# mimic4688.net
KiCad netlist of a schematic drawn in EAGLE
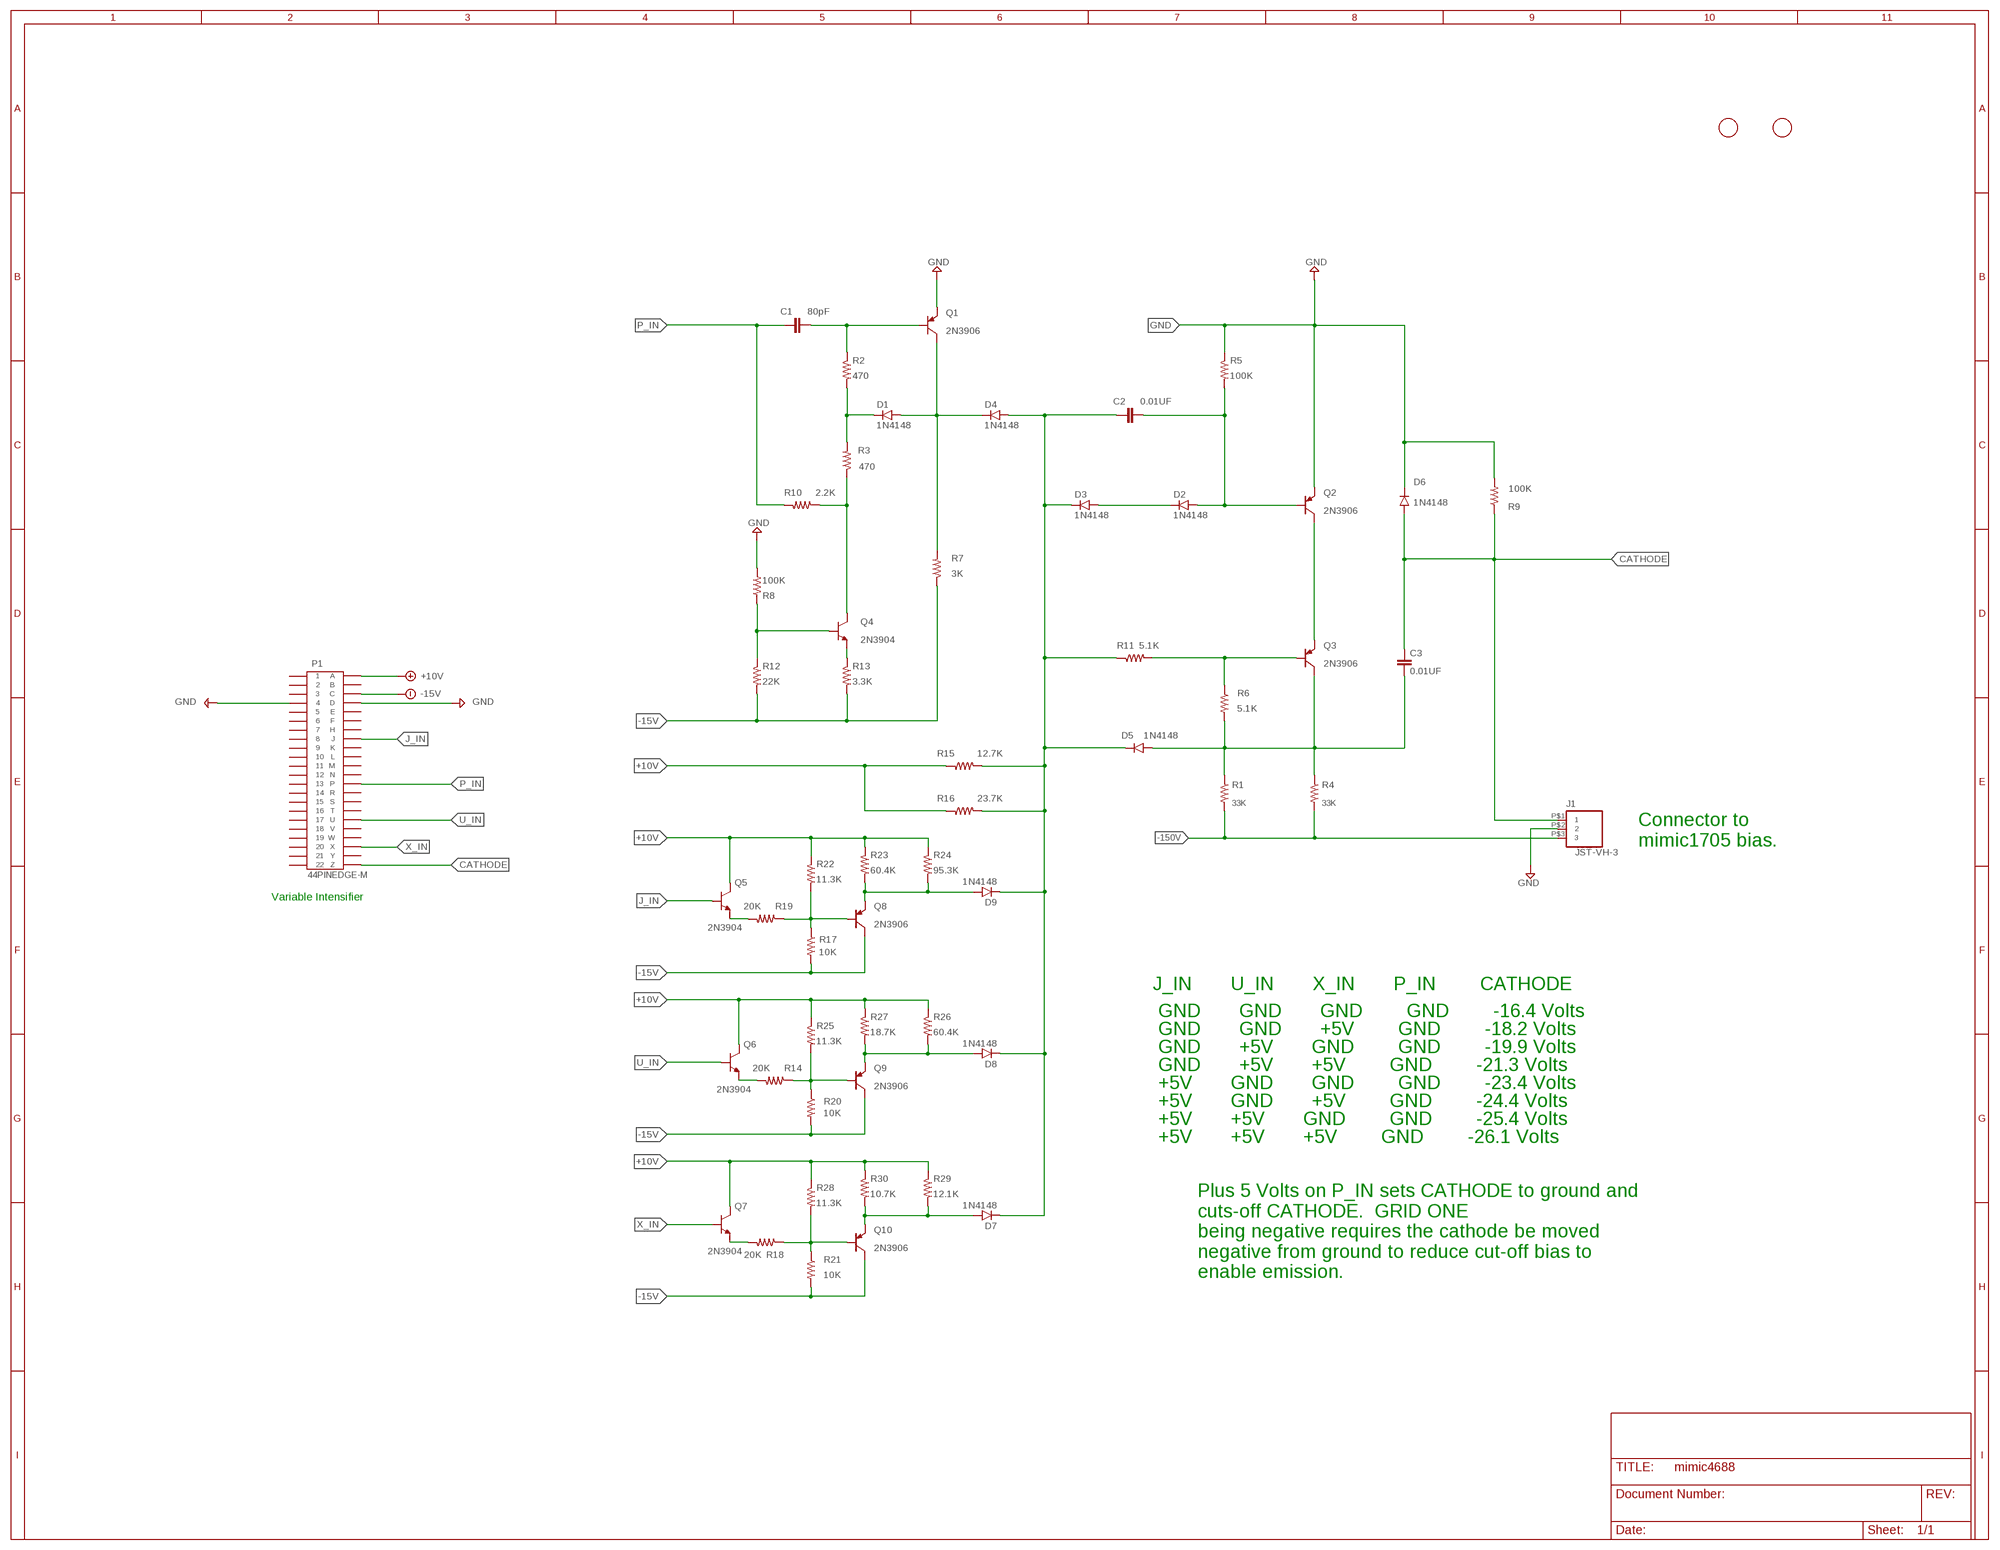
[diagram p0: schematic, sheet 1]

(export (version "E")
  (design (tool "Eeschema 10.0.6"))
  (components
    (comp (ref "C1")
      (value "80pF")
      (footprint "eagle-import:5MM_TH")
      (libsource (lib "eagle-import") (part "CAP_5MM"))
    )
    (comp (ref "C2")
      (value "0.01UF")
      (footprint "eagle-import:5MM_TH")
      (libsource (lib "eagle-import") (part "CAP_5MM"))
    )
    (comp (ref "C3")
      (value "0.01UF")
      (footprint "eagle-import:5MM_TH")
      (libsource (lib "eagle-import") (part "CAP_5MM"))
    )
    (comp (ref "D1")
      (value "1N4148")
      (footprint "eagle-import:DO35-7")
      (libsource (lib "eagle-import") (part "1N4148"))
    )
    (comp (ref "D2")
      (value "1N4148")
      (footprint "eagle-import:DO35-7")
      (libsource (lib "eagle-import") (part "1N4148"))
    )
    (comp (ref "D3")
      (value "1N4148")
      (footprint "eagle-import:DO35-7")
      (libsource (lib "eagle-import") (part "1N4148"))
    )
    (comp (ref "D4")
      (value "1N4148")
      (footprint "eagle-import:DO35-7")
      (libsource (lib "eagle-import") (part "1N4148"))
    )
    (comp (ref "D5")
      (value "1N4148")
      (footprint "eagle-import:DO35-7")
      (libsource (lib "eagle-import") (part "1N4148"))
    )
    (comp (ref "D6")
      (value "1N4148")
      (footprint "eagle-import:DO35-7")
      (libsource (lib "eagle-import") (part "1N4148"))
    )
    (comp (ref "D7")
      (value "1N4148")
      (footprint "eagle-import:DO35-7")
      (libsource (lib "eagle-import") (part "1N4148"))
    )
    (comp (ref "D8")
      (value "1N4148")
      (footprint "eagle-import:DO35-7")
      (libsource (lib "eagle-import") (part "1N4148"))
    )
    (comp (ref "D9")
      (value "1N4148")
      (footprint "eagle-import:DO35-7")
      (libsource (lib "eagle-import") (part "1N4148"))
    )
    (comp (ref "J1")
      (value "JST-VH-3")
      (footprint "eagle-import:VHR-3N")
      (libsource (lib "eagle-import") (part "JST-VH-3"))
    )
    (comp (ref "P1")
      (value "44PINEDGE-M")
      (footprint "eagle-import:44PINEDGE")
      (libsource (lib "eagle-import") (part "44PINEDGE-M"))
    )
    (comp (ref "Q1")
      (value "2N3906")
      (footprint "eagle-import:TO92")
      (libsource (lib "eagle-import") (part "2N3906"))
    )
    (comp (ref "Q2")
      (value "2N3906")
      (footprint "eagle-import:TO92")
      (libsource (lib "eagle-import") (part "2N3906"))
    )
    (comp (ref "Q3")
      (value "2N3906")
      (footprint "eagle-import:TO92")
      (libsource (lib "eagle-import") (part "2N3906"))
    )
    (comp (ref "Q4")
      (value "2N3904")
      (footprint "eagle-import:TO92")
      (libsource (lib "eagle-import") (part "2N3904"))
    )
    (comp (ref "Q5")
      (value "2N3904")
      (footprint "eagle-import:TO92")
      (libsource (lib "eagle-import") (part "2N3904"))
    )
    (comp (ref "Q6")
      (value "2N3904")
      (footprint "eagle-import:TO92")
      (libsource (lib "eagle-import") (part "2N3904"))
    )
    (comp (ref "Q7")
      (value "2N3904")
      (footprint "eagle-import:TO92")
      (libsource (lib "eagle-import") (part "2N3904"))
    )
    (comp (ref "Q8")
      (value "2N3906")
      (footprint "eagle-import:TO92")
      (libsource (lib "eagle-import") (part "2N3906"))
    )
    (comp (ref "Q9")
      (value "2N3906")
      (footprint "eagle-import:TO92")
      (libsource (lib "eagle-import") (part "2N3906"))
    )
    (comp (ref "Q10")
      (value "2N3906")
      (footprint "eagle-import:TO92")
      (libsource (lib "eagle-import") (part "2N3906"))
    )
    (comp (ref "R1")
      (value "33K")
      (footprint "eagle-import:RR02")
      (libsource (lib "eagle-import") (part "RES33K2W"))
    )
    (comp (ref "R2")
      (value "470")
      (footprint "eagle-import:0207_10")
      (libsource (lib "eagle-import") (part "R-1/4WATT"))
    )
    (comp (ref "R3")
      (value "470")
      (footprint "eagle-import:0207_10")
      (libsource (lib "eagle-import") (part "R-1/4WATT"))
    )
    (comp (ref "R4")
      (value "33K")
      (footprint "eagle-import:RR02")
      (libsource (lib "eagle-import") (part "RES33K2W"))
    )
    (comp (ref "R5")
      (value "100K")
      (footprint "eagle-import:0207_10")
      (libsource (lib "eagle-import") (part "R-1/4WATT"))
    )
    (comp (ref "R6")
      (value "5.1K")
      (footprint "eagle-import:0207_10")
      (libsource (lib "eagle-import") (part "R-1/4WATT"))
    )
    (comp (ref "R7")
      (value "3K")
      (footprint "eagle-import:0207_10")
      (libsource (lib "eagle-import") (part "R-1/4WATT"))
    )
    (comp (ref "R8")
      (value "100K")
      (footprint "eagle-import:0207_10")
      (libsource (lib "eagle-import") (part "R-1/4WATT"))
    )
    (comp (ref "R9")
      (value "100K")
      (footprint "eagle-import:0207_10")
      (libsource (lib "eagle-import") (part "R-1/4WATT"))
    )
    (comp (ref "R10")
      (value "2.2K")
      (footprint "eagle-import:0207_10")
      (libsource (lib "eagle-import") (part "R-1/4WATT"))
    )
    (comp (ref "R11")
      (value "5.1K")
      (footprint "eagle-import:0207_10")
      (libsource (lib "eagle-import") (part "R-1/4WATT"))
    )
    (comp (ref "R12")
      (value "22K")
      (footprint "eagle-import:0207_10")
      (libsource (lib "eagle-import") (part "R-1/4WATT"))
    )
    (comp (ref "R13")
      (value "3.3K")
      (footprint "eagle-import:0207_10")
      (libsource (lib "eagle-import") (part "R-1/4WATT"))
    )
    (comp (ref "R14")
      (value "20K")
      (footprint "eagle-import:0207_10")
      (libsource (lib "eagle-import") (part "R-1/4WATT"))
    )
    (comp (ref "R15")
      (value "12.7K")
      (footprint "eagle-import:0207_10")
      (libsource (lib "eagle-import") (part "R-1/4WATT"))
    )
    (comp (ref "R16")
      (value "23.7K")
      (footprint "eagle-import:0207_10")
      (libsource (lib "eagle-import") (part "R-1/4WATT"))
    )
    (comp (ref "R17")
      (value "10K")
      (footprint "eagle-import:0207_10")
      (libsource (lib "eagle-import") (part "R-1/4WATT"))
    )
    (comp (ref "R18")
      (value "20K")
      (footprint "eagle-import:0207_10")
      (libsource (lib "eagle-import") (part "R-1/4WATT"))
    )
    (comp (ref "R19")
      (value "20K")
      (footprint "eagle-import:0207_10")
      (libsource (lib "eagle-import") (part "R-1/4WATT"))
    )
    (comp (ref "R20")
      (value "10K")
      (footprint "eagle-import:0207_10")
      (libsource (lib "eagle-import") (part "R-1/4WATT"))
    )
    (comp (ref "R21")
      (value "10K")
      (footprint "eagle-import:0207_10")
      (libsource (lib "eagle-import") (part "R-1/4WATT"))
    )
    (comp (ref "R22")
      (value "11.3K")
      (footprint "eagle-import:0207_10")
      (libsource (lib "eagle-import") (part "R-1/4WATT"))
    )
    (comp (ref "R23")
      (value "60.4K")
      (footprint "eagle-import:0207_10")
      (libsource (lib "eagle-import") (part "R-1/4WATT"))
    )
    (comp (ref "R24")
      (value "95.3K")
      (footprint "eagle-import:0207_10")
      (libsource (lib "eagle-import") (part "R-1/4WATT"))
    )
    (comp (ref "R25")
      (value "11.3K")
      (footprint "eagle-import:0207_10")
      (libsource (lib "eagle-import") (part "R-1/4WATT"))
    )
    (comp (ref "R26")
      (value "60.4K")
      (footprint "eagle-import:0207_10")
      (libsource (lib "eagle-import") (part "R-1/4WATT"))
    )
    (comp (ref "R27")
      (value "18.7K")
      (footprint "eagle-import:0207_10")
      (libsource (lib "eagle-import") (part "R-1/4WATT"))
    )
    (comp (ref "R28")
      (value "11.3K")
      (footprint "eagle-import:0207_10")
      (libsource (lib "eagle-import") (part "R-1/4WATT"))
    )
    (comp (ref "R29")
      (value "12.1K")
      (footprint "eagle-import:0207_10")
      (libsource (lib "eagle-import") (part "R-1/4WATT"))
    )
    (comp (ref "R30")
      (value "10.7K")
      (footprint "eagle-import:0207_10")
      (libsource (lib "eagle-import") (part "R-1/4WATT"))
    )
    (comp (ref "U$1")
      (value "FIDUCIAL")
      (footprint "eagle-import:FIDUCIAL_1MM")
      (libsource (lib "eagle-import") (part "FIDUCIAL"))
    )
    (comp (ref "U$2")
      (value "FIDUCIAL")
      (footprint "eagle-import:FIDUCIAL_1MM")
      (libsource (lib "eagle-import") (part "FIDUCIAL"))
    )
  )
  (nets
    (net (code "1") (name "+10V") (class "Default")
      (node (ref "P1") (pin "A") (pinfunction "A_A") (pintype "passive"))
      (node (ref "Q5") (pin "3") (pinfunction "C_3") (pintype "passive"))
      (node (ref "Q6") (pin "3") (pinfunction "C_3") (pintype "passive"))
      (node (ref "Q7") (pin "3") (pinfunction "C_3") (pintype "passive"))
      (node (ref "R15") (pin "1") (pinfunction "P$1_1") (pintype "passive"))
      (node (ref "R16") (pin "1") (pinfunction "P$1_1") (pintype "passive"))
      (node (ref "R22") (pin "1") (pinfunction "P$1_1") (pintype "passive"))
      (node (ref "R23") (pin "1") (pinfunction "P$1_1") (pintype "passive"))
      (node (ref "R24") (pin "1") (pinfunction "P$1_1") (pintype "passive"))
      (node (ref "R25") (pin "1") (pinfunction "P$1_1") (pintype "passive"))
      (node (ref "R26") (pin "1") (pinfunction "P$1_1") (pintype "passive"))
      (node (ref "R27") (pin "1") (pinfunction "P$1_1") (pintype "passive"))
      (node (ref "R28") (pin "1") (pinfunction "P$1_1") (pintype "passive"))
      (node (ref "R29") (pin "1") (pinfunction "P$1_1") (pintype "passive"))
      (node (ref "R30") (pin "1") (pinfunction "P$1_1") (pintype "passive"))
    )
    (net (code "2") (name "-15V") (class "Default")
      (node (ref "P1") (pin "C") (pinfunction "C_C") (pintype "passive"))
      (node (ref "Q10") (pin "1") (pinfunction "C_1") (pintype "passive"))
      (node (ref "Q8") (pin "1") (pinfunction "C_1") (pintype "passive"))
      (node (ref "Q9") (pin "1") (pinfunction "C_1") (pintype "passive"))
      (node (ref "R12") (pin "2") (pinfunction "P$2_2") (pintype "passive"))
      (node (ref "R13") (pin "2") (pinfunction "P$2_2") (pintype "passive"))
      (node (ref "R17") (pin "2") (pinfunction "P$2_2") (pintype "passive"))
      (node (ref "R20") (pin "2") (pinfunction "P$2_2") (pintype "passive"))
      (node (ref "R21") (pin "2") (pinfunction "P$2_2") (pintype "passive"))
      (node (ref "R7") (pin "1") (pinfunction "P$1_1") (pintype "passive"))
    )
    (net (code "3") (name "-150V") (class "Default")
      (node (ref "J1") (pin "P$3") (pinfunction "3_P$3") (pintype "bidirectional"))
      (node (ref "R1") (pin "2") (pinfunction "P$2_2") (pintype "passive"))
      (node (ref "R4") (pin "2") (pinfunction "P$2_2") (pintype "passive"))
    )
    (net (code "4") (name "CATHODE") (class "Default")
      (node (ref "C3") (pin "1") (pinfunction "1_1") (pintype "passive"))
      (node (ref "D6") (pin "A") (pinfunction "A_A") (pintype "passive"))
      (node (ref "J1") (pin "P$1") (pinfunction "1_P$1") (pintype "bidirectional"))
      (node (ref "P1") (pin "Z") (pinfunction "Z_Z") (pintype "passive"))
      (node (ref "R9") (pin "1") (pinfunction "P$1_1") (pintype "passive"))
    )
    (net (code "5") (name "GND") (class "Default")
      (node (ref "D6") (pin "C") (pinfunction "C_C") (pintype "passive"))
      (node (ref "J1") (pin "P$2") (pinfunction "2_P$2") (pintype "bidirectional"))
      (node (ref "P1") (pin "4") (pinfunction "4_4") (pintype "passive"))
      (node (ref "P1") (pin "D") (pinfunction "D_D") (pintype "passive"))
      (node (ref "Q1") (pin "3") (pinfunction "E_3") (pintype "passive"))
      (node (ref "Q2") (pin "3") (pinfunction "E_3") (pintype "passive"))
      (node (ref "R5") (pin "1") (pinfunction "P$1_1") (pintype "passive"))
      (node (ref "R8") (pin "2") (pinfunction "P$2_2") (pintype "passive"))
      (node (ref "R9") (pin "2") (pinfunction "P$2_2") (pintype "passive"))
    )
    (net (code "6") (name "J_IN") (class "Default")
      (node (ref "P1") (pin "J") (pinfunction "J_J") (pintype "passive"))
      (node (ref "Q5") (pin "2") (pinfunction "B_2") (pintype "passive"))
    )
    (net (code "7") (name "Net-(D2-PadC)") (class "Default")
      (node (ref "D2") (pin "C") (pinfunction "C_C") (pintype "passive"))
      (node (ref "D3") (pin "A") (pinfunction "A_A") (pintype "passive"))
    )
    (net (code "8") (name "Net-(Q1-B)") (class "Default")
      (node (ref "C1") (pin "2") (pinfunction "2_2") (pintype "passive"))
      (node (ref "Q1") (pin "2") (pinfunction "B_2") (pintype "passive"))
      (node (ref "R2") (pin "1") (pinfunction "P$1_1") (pintype "passive"))
    )
    (net (code "9") (name "Net-(Q1-C)") (class "Default")
      (node (ref "D1") (pin "A") (pinfunction "A_A") (pintype "passive"))
      (node (ref "D4") (pin "C") (pinfunction "C_C") (pintype "passive"))
      (node (ref "Q1") (pin "1") (pinfunction "C_1") (pintype "passive"))
      (node (ref "R7") (pin "2") (pinfunction "P$2_2") (pintype "passive"))
    )
    (net (code "10") (name "Net-(Q2-B)") (class "Default")
      (node (ref "C2") (pin "2") (pinfunction "2_2") (pintype "passive"))
      (node (ref "D2") (pin "A") (pinfunction "A_A") (pintype "passive"))
      (node (ref "Q2") (pin "2") (pinfunction "B_2") (pintype "passive"))
      (node (ref "R5") (pin "2") (pinfunction "P$2_2") (pintype "passive"))
    )
    (net (code "11") (name "Net-(Q2-C)") (class "Default")
      (node (ref "Q2") (pin "1") (pinfunction "C_1") (pintype "passive"))
      (node (ref "Q3") (pin "3") (pinfunction "E_3") (pintype "passive"))
    )
    (net (code "12") (name "Net-(Q3-B)") (class "Default")
      (node (ref "Q3") (pin "2") (pinfunction "B_2") (pintype "passive"))
      (node (ref "R11") (pin "2") (pinfunction "P$2_2") (pintype "passive"))
      (node (ref "R6") (pin "1") (pinfunction "P$1_1") (pintype "passive"))
    )
    (net (code "13") (name "Net-(Q3-C)") (class "Default")
      (node (ref "C3") (pin "2") (pinfunction "2_2") (pintype "passive"))
      (node (ref "D5") (pin "A") (pinfunction "A_A") (pintype "passive"))
      (node (ref "Q3") (pin "1") (pinfunction "C_1") (pintype "passive"))
      (node (ref "R1") (pin "1") (pinfunction "P$1_1") (pintype "passive"))
      (node (ref "R4") (pin "1") (pinfunction "P$1_1") (pintype "passive"))
      (node (ref "R6") (pin "2") (pinfunction "P$2_2") (pintype "passive"))
    )
    (net (code "14") (name "Net-(Q4-B)") (class "Default")
      (node (ref "Q4") (pin "2") (pinfunction "B_2") (pintype "passive"))
      (node (ref "R12") (pin "1") (pinfunction "P$1_1") (pintype "passive"))
      (node (ref "R8") (pin "1") (pinfunction "P$1_1") (pintype "passive"))
    )
    (net (code "15") (name "Net-(Q4-C)") (class "Default")
      (node (ref "Q4") (pin "3") (pinfunction "C_3") (pintype "passive"))
      (node (ref "R10") (pin "1") (pinfunction "P$1_1") (pintype "passive"))
      (node (ref "R3") (pin "1") (pinfunction "P$1_1") (pintype "passive"))
    )
    (net (code "16") (name "Net-(Q4-E)") (class "Default")
      (node (ref "Q4") (pin "1") (pinfunction "E_1") (pintype "passive"))
      (node (ref "R13") (pin "1") (pinfunction "P$1_1") (pintype "passive"))
    )
    (net (code "17") (name "Net-(Q5-E)") (class "Default")
      (node (ref "Q5") (pin "1") (pinfunction "E_1") (pintype "passive"))
      (node (ref "R19") (pin "2") (pinfunction "P$2_2") (pintype "passive"))
    )
    (net (code "18") (name "Net-(Q6-E)") (class "Default")
      (node (ref "Q6") (pin "1") (pinfunction "E_1") (pintype "passive"))
      (node (ref "R14") (pin "2") (pinfunction "P$2_2") (pintype "passive"))
    )
    (net (code "19") (name "Net-(Q7-E)") (class "Default")
      (node (ref "Q7") (pin "1") (pinfunction "E_1") (pintype "passive"))
      (node (ref "R18") (pin "2") (pinfunction "P$2_2") (pintype "passive"))
    )
    (net (code "20") (name "Net-(Q8-B)") (class "Default")
      (node (ref "Q8") (pin "2") (pinfunction "B_2") (pintype "passive"))
      (node (ref "R17") (pin "1") (pinfunction "P$1_1") (pintype "passive"))
      (node (ref "R19") (pin "1") (pinfunction "P$1_1") (pintype "passive"))
      (node (ref "R22") (pin "2") (pinfunction "P$2_2") (pintype "passive"))
    )
    (net (code "21") (name "Net-(Q8-E)") (class "Default")
      (node (ref "D9") (pin "A") (pinfunction "A_A") (pintype "passive"))
      (node (ref "Q8") (pin "3") (pinfunction "E_3") (pintype "passive"))
      (node (ref "R23") (pin "2") (pinfunction "P$2_2") (pintype "passive"))
      (node (ref "R24") (pin "2") (pinfunction "P$2_2") (pintype "passive"))
    )
    (net (code "22") (name "Net-(Q9-B)") (class "Default")
      (node (ref "Q9") (pin "2") (pinfunction "B_2") (pintype "passive"))
      (node (ref "R14") (pin "1") (pinfunction "P$1_1") (pintype "passive"))
      (node (ref "R20") (pin "1") (pinfunction "P$1_1") (pintype "passive"))
      (node (ref "R25") (pin "2") (pinfunction "P$2_2") (pintype "passive"))
    )
    (net (code "23") (name "Net-(Q9-E)") (class "Default")
      (node (ref "D8") (pin "A") (pinfunction "A_A") (pintype "passive"))
      (node (ref "Q9") (pin "3") (pinfunction "E_3") (pintype "passive"))
      (node (ref "R26") (pin "2") (pinfunction "P$2_2") (pintype "passive"))
      (node (ref "R27") (pin "2") (pinfunction "P$2_2") (pintype "passive"))
    )
    (net (code "24") (name "Net-(Q10-B)") (class "Default")
      (node (ref "Q10") (pin "2") (pinfunction "B_2") (pintype "passive"))
      (node (ref "R18") (pin "1") (pinfunction "P$1_1") (pintype "passive"))
      (node (ref "R21") (pin "1") (pinfunction "P$1_1") (pintype "passive"))
      (node (ref "R28") (pin "2") (pinfunction "P$2_2") (pintype "passive"))
    )
    (net (code "25") (name "Net-(Q10-E)") (class "Default")
      (node (ref "D7") (pin "A") (pinfunction "A_A") (pintype "passive"))
      (node (ref "Q10") (pin "3") (pinfunction "E_3") (pintype "passive"))
      (node (ref "R29") (pin "2") (pinfunction "P$2_2") (pintype "passive"))
      (node (ref "R30") (pin "2") (pinfunction "P$2_2") (pintype "passive"))
    )
    (net (code "26") (name "Net-(R2-P$2)") (class "Default")
      (node (ref "D1") (pin "C") (pinfunction "C_C") (pintype "passive"))
      (node (ref "R2") (pin "2") (pinfunction "P$2_2") (pintype "passive"))
      (node (ref "R3") (pin "2") (pinfunction "P$2_2") (pintype "passive"))
    )
    (net (code "27") (name "Net-(R11-P$1)") (class "Default")
      (node (ref "C2") (pin "1") (pinfunction "1_1") (pintype "passive"))
      (node (ref "D3") (pin "C") (pinfunction "C_C") (pintype "passive"))
      (node (ref "D4") (pin "A") (pinfunction "A_A") (pintype "passive"))
      (node (ref "D5") (pin "C") (pinfunction "C_C") (pintype "passive"))
      (node (ref "D7") (pin "C") (pinfunction "C_C") (pintype "passive"))
      (node (ref "D8") (pin "C") (pinfunction "C_C") (pintype "passive"))
      (node (ref "D9") (pin "C") (pinfunction "C_C") (pintype "passive"))
      (node (ref "R11") (pin "1") (pinfunction "P$1_1") (pintype "passive"))
      (node (ref "R15") (pin "2") (pinfunction "P$2_2") (pintype "passive"))
      (node (ref "R16") (pin "2") (pinfunction "P$2_2") (pintype "passive"))
    )
    (net (code "28") (name "P_IN") (class "Default")
      (node (ref "C1") (pin "1") (pinfunction "1_1") (pintype "passive"))
      (node (ref "P1") (pin "P") (pinfunction "P_P") (pintype "passive"))
      (node (ref "R10") (pin "2") (pinfunction "P$2_2") (pintype "passive"))
    )
    (net (code "29") (name "U_IN") (class "Default")
      (node (ref "P1") (pin "U") (pinfunction "U_U") (pintype "passive"))
      (node (ref "Q6") (pin "2") (pinfunction "B_2") (pintype "passive"))
    )
    (net (code "30") (name "X_IN") (class "Default")
      (node (ref "P1") (pin "X") (pinfunction "X_X") (pintype "passive"))
      (node (ref "Q7") (pin "2") (pinfunction "B_2") (pintype "passive"))
    )
    (net (code "31") (name "unconnected-(P1-Pad1)") (class "Default")
      (node (ref "P1") (pin "1") (pinfunction "1_1") (pintype "passive"))
    )
    (net (code "32") (name "unconnected-(P1-Pad2)") (class "Default")
      (node (ref "P1") (pin "2") (pinfunction "2_2") (pintype "passive"))
    )
    (net (code "33") (name "unconnected-(P1-Pad3)") (class "Default")
      (node (ref "P1") (pin "3") (pinfunction "3_3") (pintype "passive"))
    )
    (net (code "34") (name "unconnected-(P1-Pad5)") (class "Default")
      (node (ref "P1") (pin "5") (pinfunction "5_5") (pintype "passive"))
    )
    (net (code "35") (name "unconnected-(P1-Pad6)") (class "Default")
      (node (ref "P1") (pin "6") (pinfunction "6_6") (pintype "passive"))
    )
    (net (code "36") (name "unconnected-(P1-Pad7)") (class "Default")
      (node (ref "P1") (pin "7") (pinfunction "7_7") (pintype "passive"))
    )
    (net (code "37") (name "unconnected-(P1-Pad8)") (class "Default")
      (node (ref "P1") (pin "8") (pinfunction "8_8") (pintype "passive"))
    )
    (net (code "38") (name "unconnected-(P1-Pad9)") (class "Default")
      (node (ref "P1") (pin "9") (pinfunction "9_9") (pintype "passive"))
    )
    (net (code "39") (name "unconnected-(P1-Pad10)") (class "Default")
      (node (ref "P1") (pin "10") (pinfunction "10_10") (pintype "passive"))
    )
    (net (code "40") (name "unconnected-(P1-Pad11)") (class "Default")
      (node (ref "P1") (pin "11") (pinfunction "11_11") (pintype "passive"))
    )
    (net (code "41") (name "unconnected-(P1-Pad12)") (class "Default")
      (node (ref "P1") (pin "12") (pinfunction "12_12") (pintype "passive"))
    )
    (net (code "42") (name "unconnected-(P1-Pad13)") (class "Default")
      (node (ref "P1") (pin "13") (pinfunction "13_13") (pintype "passive"))
    )
    (net (code "43") (name "unconnected-(P1-Pad14)") (class "Default")
      (node (ref "P1") (pin "14") (pinfunction "14_14") (pintype "passive"))
    )
    (net (code "44") (name "unconnected-(P1-Pad15)") (class "Default")
      (node (ref "P1") (pin "15") (pinfunction "15_15") (pintype "passive"))
    )
    (net (code "45") (name "unconnected-(P1-Pad16)") (class "Default")
      (node (ref "P1") (pin "16") (pinfunction "16_16") (pintype "passive"))
    )
    (net (code "46") (name "unconnected-(P1-Pad17)") (class "Default")
      (node (ref "P1") (pin "17") (pinfunction "17_17") (pintype "passive"))
    )
    (net (code "47") (name "unconnected-(P1-Pad18)") (class "Default")
      (node (ref "P1") (pin "18") (pinfunction "18_18") (pintype "passive"))
    )
    (net (code "48") (name "unconnected-(P1-Pad19)") (class "Default")
      (node (ref "P1") (pin "19") (pinfunction "19_19") (pintype "passive"))
    )
    (net (code "49") (name "unconnected-(P1-Pad20)") (class "Default")
      (node (ref "P1") (pin "20") (pinfunction "20_20") (pintype "passive"))
    )
    (net (code "50") (name "unconnected-(P1-Pad21)") (class "Default")
      (node (ref "P1") (pin "21") (pinfunction "21_21") (pintype "passive"))
    )
    (net (code "51") (name "unconnected-(P1-Pad22)") (class "Default")
      (node (ref "P1") (pin "22") (pinfunction "22_22") (pintype "passive"))
    )
    (net (code "52") (name "unconnected-(P1-PadB)") (class "Default")
      (node (ref "P1") (pin "B") (pinfunction "B_B") (pintype "passive"))
    )
    (net (code "53") (name "unconnected-(P1-PadE)") (class "Default")
      (node (ref "P1") (pin "E") (pinfunction "E_E") (pintype "passive"))
    )
    (net (code "54") (name "unconnected-(P1-PadF)") (class "Default")
      (node (ref "P1") (pin "F") (pinfunction "F_F") (pintype "passive"))
    )
    (net (code "55") (name "unconnected-(P1-PadH)") (class "Default")
      (node (ref "P1") (pin "H") (pinfunction "H_H") (pintype "passive"))
    )
    (net (code "56") (name "unconnected-(P1-PadK)") (class "Default")
      (node (ref "P1") (pin "K") (pinfunction "K_K") (pintype "passive"))
    )
    (net (code "57") (name "unconnected-(P1-PadL)") (class "Default")
      (node (ref "P1") (pin "L") (pinfunction "L_L") (pintype "passive"))
    )
    (net (code "58") (name "unconnected-(P1-PadM)") (class "Default")
      (node (ref "P1") (pin "M") (pinfunction "M_M") (pintype "passive"))
    )
    (net (code "59") (name "unconnected-(P1-PadN)") (class "Default")
      (node (ref "P1") (pin "N") (pinfunction "N_N") (pintype "passive"))
    )
    (net (code "60") (name "unconnected-(P1-PadR)") (class "Default")
      (node (ref "P1") (pin "R") (pinfunction "R_R") (pintype "passive"))
    )
    (net (code "61") (name "unconnected-(P1-PadS)") (class "Default")
      (node (ref "P1") (pin "S") (pinfunction "S_S") (pintype "passive"))
    )
    (net (code "62") (name "unconnected-(P1-PadT)") (class "Default")
      (node (ref "P1") (pin "T") (pinfunction "T_T") (pintype "passive"))
    )
    (net (code "63") (name "unconnected-(P1-PadV)") (class "Default")
      (node (ref "P1") (pin "V") (pinfunction "V_V") (pintype "passive"))
    )
    (net (code "64") (name "unconnected-(P1-PadW)") (class "Default")
      (node (ref "P1") (pin "W") (pinfunction "W_W") (pintype "passive"))
    )
    (net (code "65") (name "unconnected-(P1-PadY)") (class "Default")
      (node (ref "P1") (pin "Y") (pinfunction "Y_Y") (pintype "passive"))
    )
  )
)
